# Blinky_Buildings_-_Empire_State_Building.net
KiCad netlist of a schematic drawn in EAGLE
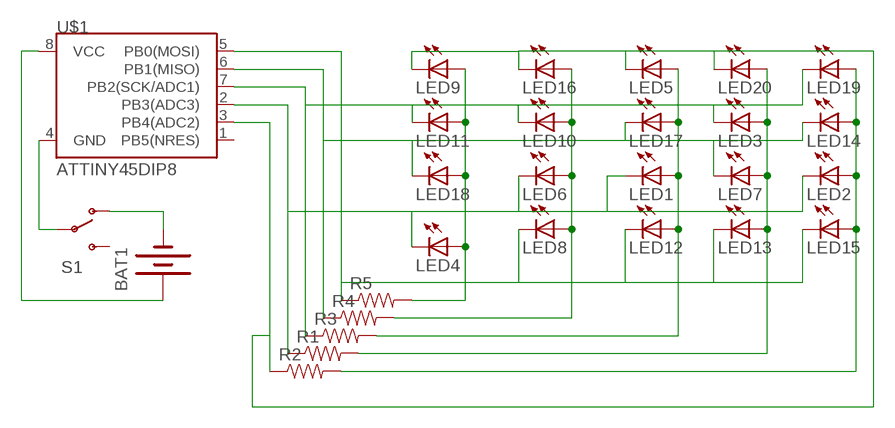
[diagram p0: schematic, sheet 1]

(export (version "E")
  (design (tool "Eeschema 10.0.6"))
  (components
    (comp (ref "BAT1")
      (value "BATTERY20PTH")
      (footprint "eagle-import:BATTCOM_20MM_PTH")
      (libsource (lib "eagle-import") (part "BATTERY20PTH"))
    )
    (comp (ref "LED1")
      (value "LED3MM")
      (footprint "eagle-import:LED3MM")
      (libsource (lib "eagle-import") (part "LED3MM"))
    )
    (comp (ref "LED2")
      (value "LED3MM")
      (footprint "eagle-import:LED3MM")
      (libsource (lib "eagle-import") (part "LED3MM"))
    )
    (comp (ref "LED3")
      (value "LED3MM")
      (footprint "eagle-import:LED3MM")
      (libsource (lib "eagle-import") (part "LED3MM"))
    )
    (comp (ref "LED4")
      (value "LED3MM")
      (footprint "eagle-import:LED3MM")
      (libsource (lib "eagle-import") (part "LED3MM"))
    )
    (comp (ref "LED5")
      (value "LED3MM")
      (footprint "eagle-import:LED3MM")
      (libsource (lib "eagle-import") (part "LED3MM"))
    )
    (comp (ref "LED6")
      (value "LED3MM")
      (footprint "eagle-import:LED3MM")
      (libsource (lib "eagle-import") (part "LED3MM"))
    )
    (comp (ref "LED7")
      (value "LED3MM")
      (footprint "eagle-import:LED3MM")
      (libsource (lib "eagle-import") (part "LED3MM"))
    )
    (comp (ref "LED8")
      (value "LED3MM")
      (footprint "eagle-import:LED3MM")
      (libsource (lib "eagle-import") (part "LED3MM"))
    )
    (comp (ref "LED9")
      (value "LED3MM")
      (footprint "eagle-import:LED3MM")
      (libsource (lib "eagle-import") (part "LED3MM"))
    )
    (comp (ref "LED10")
      (value "LED3MM")
      (footprint "eagle-import:LED3MM")
      (libsource (lib "eagle-import") (part "LED3MM"))
    )
    (comp (ref "LED11")
      (value "LED3MM")
      (footprint "eagle-import:LED3MM")
      (libsource (lib "eagle-import") (part "LED3MM"))
    )
    (comp (ref "LED12")
      (value "LED3MM")
      (footprint "eagle-import:LED3MM")
      (libsource (lib "eagle-import") (part "LED3MM"))
    )
    (comp (ref "LED13")
      (value "LED3MM")
      (footprint "eagle-import:LED3MM")
      (libsource (lib "eagle-import") (part "LED3MM"))
    )
    (comp (ref "LED14")
      (value "LED3MM")
      (footprint "eagle-import:LED3MM")
      (libsource (lib "eagle-import") (part "LED3MM"))
    )
    (comp (ref "LED15")
      (value "LED3MM")
      (footprint "eagle-import:LED3MM")
      (libsource (lib "eagle-import") (part "LED3MM"))
    )
    (comp (ref "LED16")
      (value "LED3MM")
      (footprint "eagle-import:LED3MM")
      (libsource (lib "eagle-import") (part "LED3MM"))
    )
    (comp (ref "LED17")
      (value "LED3MM")
      (footprint "eagle-import:LED3MM")
      (libsource (lib "eagle-import") (part "LED3MM"))
    )
    (comp (ref "LED18")
      (value "LED3MM")
      (footprint "eagle-import:LED3MM")
      (libsource (lib "eagle-import") (part "LED3MM"))
    )
    (comp (ref "LED19")
      (value "LED3MM")
      (footprint "eagle-import:LED3MM")
      (libsource (lib "eagle-import") (part "LED3MM"))
    )
    (comp (ref "LED20")
      (value "LED3MM")
      (footprint "eagle-import:LED3MM")
      (libsource (lib "eagle-import") (part "LED3MM"))
    )
    (comp (ref "R1")
      (value "RESISTORAXIAL-0.3")
      (footprint "eagle-import:AXIAL-0.3")
      (libsource (lib "eagle-import") (part "RESISTORAXIAL-0.3"))
    )
    (comp (ref "R2")
      (value "RESISTORAXIAL-0.3")
      (footprint "eagle-import:AXIAL-0.3")
      (libsource (lib "eagle-import") (part "RESISTORAXIAL-0.3"))
    )
    (comp (ref "R3")
      (value "RESISTORAXIAL-0.3")
      (footprint "eagle-import:AXIAL-0.3")
      (libsource (lib "eagle-import") (part "RESISTORAXIAL-0.3"))
    )
    (comp (ref "R4")
      (value "RESISTORAXIAL-0.3")
      (footprint "eagle-import:AXIAL-0.3")
      (libsource (lib "eagle-import") (part "RESISTORAXIAL-0.3"))
    )
    (comp (ref "R5")
      (value "RESISTORAXIAL-0.3")
      (footprint "eagle-import:AXIAL-0.3")
      (libsource (lib "eagle-import") (part "RESISTORAXIAL-0.3"))
    )
    (comp (ref "S1")
      (value "SWITCH-SPSTKIT")
      (footprint "eagle-import:SWITCH-SPDT_KIT")
      (libsource (lib "eagle-import") (part "SWITCH-SPSTKIT"))
    )
    (comp (ref "U$1")
      (value "ATTINY45DIP8")
      (footprint "eagle-import:DIP08")
      (libsource (lib "eagle-import") (part "ATTINY45DIP8"))
    )
  )
  (nets
    (net (code "1") (name "Net-(BAT1-+)") (class "Default")
      (node (ref "BAT1") (pin "1") (pinfunction "+_1") (pintype "power_in"))
      (node (ref "U$1") (pin "8") (pinfunction "VCC_8") (pintype "bidirectional"))
    )
    (net (code "2") (name "Net-(BAT1--)") (class "Default")
      (node (ref "BAT1") (pin "2") (pinfunction "-_2") (pintype "power_in"))
      (node (ref "S1") (pin "1") (pinfunction "O_1") (pintype "passive"))
    )
    (net (code "3") (name "Net-(LED1-C)") (class "Default")
      (node (ref "LED1") (pin "K") (pinfunction "C_K") (pintype "passive"))
      (node (ref "LED2") (pin "K") (pinfunction "C_K") (pintype "passive"))
      (node (ref "LED4") (pin "K") (pinfunction "C_K") (pintype "passive"))
      (node (ref "LED6") (pin "K") (pinfunction "C_K") (pintype "passive"))
      (node (ref "R1") (pin "P$1") (pinfunction "1_P$1") (pintype "passive"))
      (node (ref "U$1") (pin "2") (pinfunction "PB3(ADC3)_2") (pintype "bidirectional"))
    )
    (net (code "4") (name "Net-(LED10-C)") (class "Default")
      (node (ref "LED10") (pin "K") (pinfunction "C_K") (pintype "passive"))
      (node (ref "LED11") (pin "K") (pinfunction "C_K") (pintype "passive"))
      (node (ref "LED19") (pin "K") (pinfunction "C_K") (pintype "passive"))
      (node (ref "LED3") (pin "K") (pinfunction "C_K") (pintype "passive"))
      (node (ref "R3") (pin "P$1") (pinfunction "1_P$1") (pintype "passive"))
      (node (ref "U$1") (pin "7") (pinfunction "PB2(SCK/ADC1)_7") (pintype "bidirectional"))
    )
    (net (code "5") (name "Net-(LED12-C)") (class "Default")
      (node (ref "LED12") (pin "K") (pinfunction "C_K") (pintype "passive"))
      (node (ref "LED13") (pin "K") (pinfunction "C_K") (pintype "passive"))
      (node (ref "LED15") (pin "K") (pinfunction "C_K") (pintype "passive"))
      (node (ref "LED8") (pin "K") (pinfunction "C_K") (pintype "passive"))
      (node (ref "R5") (pin "P$1") (pinfunction "1_P$1") (pintype "passive"))
      (node (ref "U$1") (pin "5") (pinfunction "PB0(MOSI)_5") (pintype "bidirectional"))
    )
    (net (code "6") (name "Net-(LED14-C)") (class "Default")
      (node (ref "LED14") (pin "K") (pinfunction "C_K") (pintype "passive"))
      (node (ref "LED17") (pin "K") (pinfunction "C_K") (pintype "passive"))
      (node (ref "LED18") (pin "K") (pinfunction "C_K") (pintype "passive"))
      (node (ref "LED7") (pin "K") (pinfunction "C_K") (pintype "passive"))
      (node (ref "R4") (pin "P$1") (pinfunction "1_P$1") (pintype "passive"))
      (node (ref "U$1") (pin "6") (pinfunction "PB1(MISO)_6") (pintype "bidirectional"))
    )
    (net (code "7") (name "Net-(LED16-C)") (class "Default")
      (node (ref "LED16") (pin "K") (pinfunction "C_K") (pintype "passive"))
      (node (ref "LED20") (pin "K") (pinfunction "C_K") (pintype "passive"))
      (node (ref "LED5") (pin "K") (pinfunction "C_K") (pintype "passive"))
      (node (ref "LED9") (pin "K") (pinfunction "C_K") (pintype "passive"))
      (node (ref "R2") (pin "P$1") (pinfunction "1_P$1") (pintype "passive"))
      (node (ref "U$1") (pin "3") (pinfunction "PB4(ADC2)_3") (pintype "bidirectional"))
    )
    (net (code "8") (name "Net-(R1-2)") (class "Default")
      (node (ref "LED13") (pin "A") (pinfunction "A_A") (pintype "passive"))
      (node (ref "LED20") (pin "A") (pinfunction "A_A") (pintype "passive"))
      (node (ref "LED3") (pin "A") (pinfunction "A_A") (pintype "passive"))
      (node (ref "LED7") (pin "A") (pinfunction "A_A") (pintype "passive"))
      (node (ref "R1") (pin "P$2") (pinfunction "2_P$2") (pintype "passive"))
    )
    (net (code "9") (name "Net-(R2-2)") (class "Default")
      (node (ref "LED14") (pin "A") (pinfunction "A_A") (pintype "passive"))
      (node (ref "LED15") (pin "A") (pinfunction "A_A") (pintype "passive"))
      (node (ref "LED19") (pin "A") (pinfunction "A_A") (pintype "passive"))
      (node (ref "LED2") (pin "A") (pinfunction "A_A") (pintype "passive"))
      (node (ref "R2") (pin "P$2") (pinfunction "2_P$2") (pintype "passive"))
    )
    (net (code "10") (name "Net-(R3-2)") (class "Default")
      (node (ref "LED1") (pin "A") (pinfunction "A_A") (pintype "passive"))
      (node (ref "LED12") (pin "A") (pinfunction "A_A") (pintype "passive"))
      (node (ref "LED17") (pin "A") (pinfunction "A_A") (pintype "passive"))
      (node (ref "LED5") (pin "A") (pinfunction "A_A") (pintype "passive"))
      (node (ref "R3") (pin "P$2") (pinfunction "2_P$2") (pintype "passive"))
    )
    (net (code "11") (name "Net-(R4-2)") (class "Default")
      (node (ref "LED10") (pin "A") (pinfunction "A_A") (pintype "passive"))
      (node (ref "LED16") (pin "A") (pinfunction "A_A") (pintype "passive"))
      (node (ref "LED6") (pin "A") (pinfunction "A_A") (pintype "passive"))
      (node (ref "LED8") (pin "A") (pinfunction "A_A") (pintype "passive"))
      (node (ref "R4") (pin "P$2") (pinfunction "2_P$2") (pintype "passive"))
    )
    (net (code "12") (name "Net-(R5-2)") (class "Default")
      (node (ref "LED11") (pin "A") (pinfunction "A_A") (pintype "passive"))
      (node (ref "LED18") (pin "A") (pinfunction "A_A") (pintype "passive"))
      (node (ref "LED4") (pin "A") (pinfunction "A_A") (pintype "passive"))
      (node (ref "LED9") (pin "A") (pinfunction "A_A") (pintype "passive"))
      (node (ref "R5") (pin "P$2") (pinfunction "2_P$2") (pintype "passive"))
    )
    (net (code "13") (name "Net-(S1-P)") (class "Default")
      (node (ref "S1") (pin "2") (pinfunction "P_2") (pintype "passive"))
      (node (ref "U$1") (pin "4") (pinfunction "GND_4") (pintype "bidirectional"))
    )
    (net (code "14") (name "unconnected-(S1-S-Pad3)") (class "Default")
      (node (ref "S1") (pin "3") (pinfunction "S_3") (pintype "passive"))
    )
    (net (code "15") (name "unconnected-(U$1-PB5(NRES)-Pad1)") (class "Default")
      (node (ref "U$1") (pin "1") (pinfunction "PB5(NRES)_1") (pintype "bidirectional"))
    )
  )
)
